# MICHAv2_0.net
KiCad netlist of a schematic drawn in EAGLE
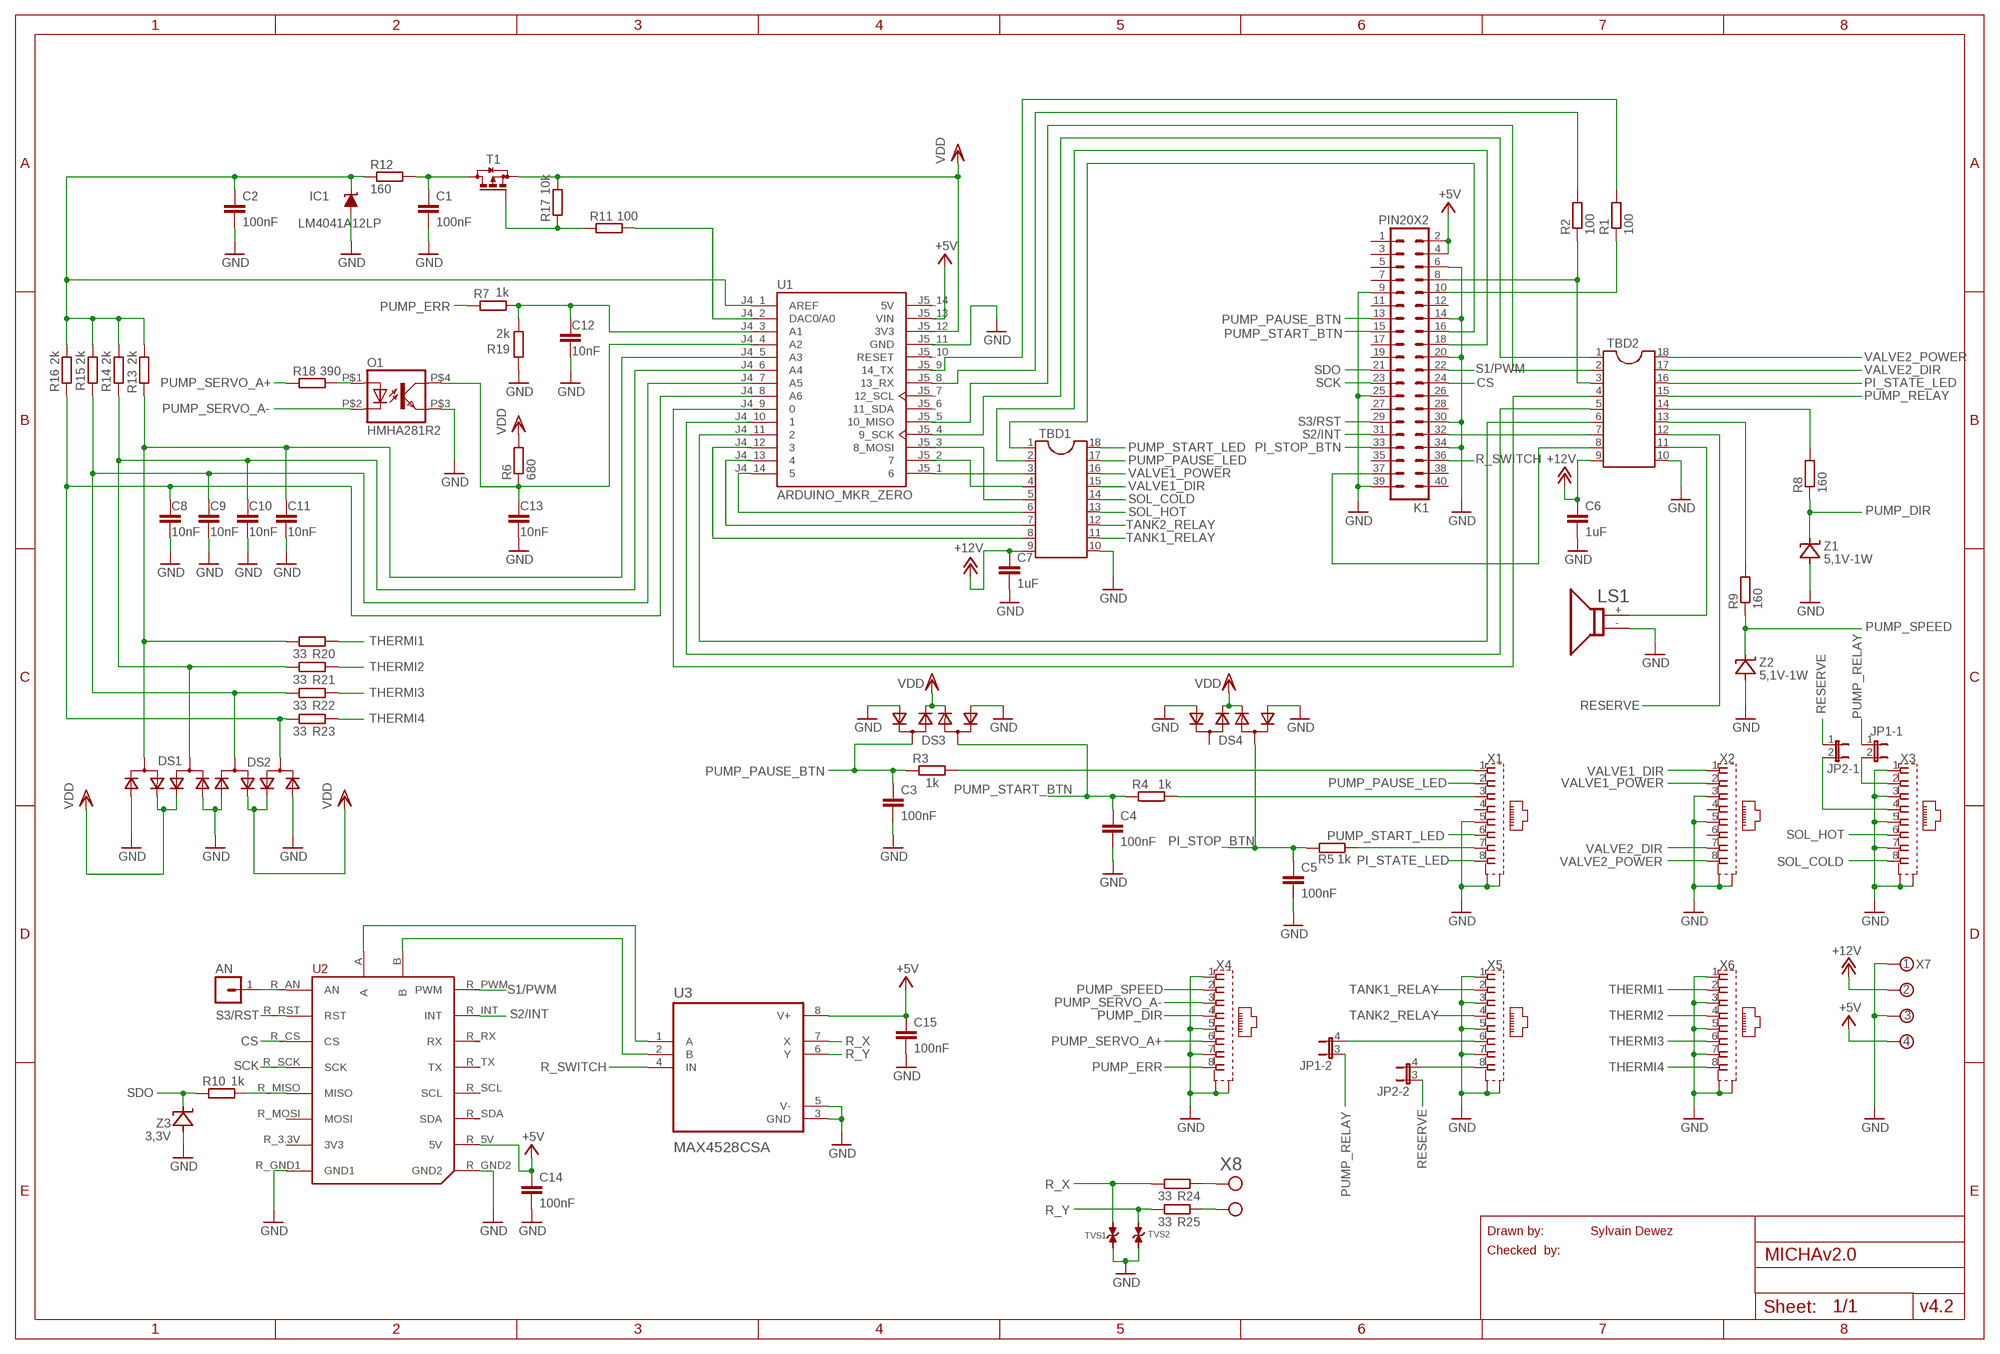
[diagram p0: schematic, sheet 1]

(export (version "E")
  (design (tool "Eeschema 10.0.6"))
  (components
    (comp (ref "AN")
      (value "MA01_PINHEADER")
      (footprint "eagle-import:MA01")
      (libsource (lib "eagle-import") (part "MA01_PINHEADER"))
    )
    (comp (ref "C1")
      (value "100nF")
      (footprint "eagle-import:C1206")
      (libsource (lib "eagle-import") (part "C-EUC1206"))
    )
    (comp (ref "C2")
      (value "100nF")
      (footprint "eagle-import:C1206")
      (libsource (lib "eagle-import") (part "C-EUC1206"))
    )
    (comp (ref "C3")
      (value "100nF")
      (footprint "eagle-import:C1206")
      (libsource (lib "eagle-import") (part "C-EUC1206"))
    )
    (comp (ref "C4")
      (value "100nF")
      (footprint "eagle-import:C1206")
      (libsource (lib "eagle-import") (part "C-EUC1206"))
    )
    (comp (ref "C5")
      (value "100nF")
      (footprint "eagle-import:C1206")
      (libsource (lib "eagle-import") (part "C-EUC1206"))
    )
    (comp (ref "C6")
      (value "1uF")
      (footprint "eagle-import:C1206")
      (libsource (lib "eagle-import") (part "C-EUC1206"))
    )
    (comp (ref "C7")
      (value "1uF")
      (footprint "eagle-import:C1206")
      (libsource (lib "eagle-import") (part "C-EUC1206"))
    )
    (comp (ref "C8")
      (value "10nF")
      (footprint "eagle-import:C1206")
      (libsource (lib "eagle-import") (part "C-EUC1206"))
    )
    (comp (ref "C9")
      (value "10nF")
      (footprint "eagle-import:C1206")
      (libsource (lib "eagle-import") (part "C-EUC1206"))
    )
    (comp (ref "C10")
      (value "10nF")
      (footprint "eagle-import:C1206")
      (libsource (lib "eagle-import") (part "C-EUC1206"))
    )
    (comp (ref "C11")
      (value "10nF")
      (footprint "eagle-import:C1206")
      (libsource (lib "eagle-import") (part "C-EUC1206"))
    )
    (comp (ref "C12")
      (value "10nF")
      (footprint "eagle-import:C1206")
      (libsource (lib "eagle-import") (part "C-EUC1206"))
    )
    (comp (ref "C13")
      (value "10nF")
      (footprint "eagle-import:C1206")
      (libsource (lib "eagle-import") (part "C-EUC1206"))
    )
    (comp (ref "C14")
      (value "100nF")
      (footprint "eagle-import:C1206")
      (libsource (lib "eagle-import") (part "C-EUC1206"))
    )
    (comp (ref "C15")
      (value "100nF")
      (footprint "eagle-import:C1206")
      (libsource (lib "eagle-import") (part "C-EUC1206"))
    )
    (comp (ref "DS1")
      (value "SDM10M45SD")
      (footprint "eagle-import:SDM10M45SD_SOT-26")
      (libsource (lib "eagle-import") (part "SDM10M45SD"))
    )
    (comp (ref "DS2")
      (value "SDM10M45SD")
      (footprint "eagle-import:SDM10M45SD_SOT-26")
      (libsource (lib "eagle-import") (part "SDM10M45SD"))
    )
    (comp (ref "DS3")
      (value "SDM10M45SD")
      (footprint "eagle-import:SDM10M45SD_SOT-26")
      (libsource (lib "eagle-import") (part "SDM10M45SD"))
    )
    (comp (ref "DS4")
      (value "SDM10M45SD")
      (footprint "eagle-import:SDM10M45SD_SOT-26")
      (libsource (lib "eagle-import") (part "SDM10M45SD"))
    )
    (comp (ref "IC1")
      (value "LM4041A12LP")
      (footprint "eagle-import:LP_O-PBCY-W3")
      (libsource (lib "eagle-import") (part "LM4041LPA12"))
    )
    (comp (ref "JP1")
      (value "JP2QE")
      (footprint "eagle-import:JP2Q")
      (libsource (lib "eagle-import") (part "JP2QE"))
    )
    (comp (ref "JP2")
      (value "JP2QE")
      (footprint "eagle-import:JP2Q")
      (libsource (lib "eagle-import") (part "JP2QE"))
    )
    (comp (ref "K1")
      (value "PIN20X2")
      (footprint "eagle-import:PIN_20X2")
      (libsource (lib "eagle-import") (part "PIN20X2"))
    )
    (comp (ref "LS1")
      (value "RSPRO-BUZZER-7800743")
      (footprint "eagle-import:RSPRO-BUZZER-7800743")
      (libsource (lib "eagle-import") (part "RSPRO-BUZZER-7800743"))
    )
    (comp (ref "O1")
      (value "HMHA281R2")
      (footprint "eagle-import:HMHA281R2")
      (libsource (lib "eagle-import") (part "HMHA281R2"))
    )
    (comp (ref "R1")
      (value "100")
      (footprint "eagle-import:R1206")
      (libsource (lib "eagle-import") (part "resistor_R-EU_R1206"))
    )
    (comp (ref "R2")
      (value "100")
      (footprint "eagle-import:R1206")
      (libsource (lib "eagle-import") (part "resistor_R-EU_R1206"))
    )
    (comp (ref "R3")
      (value "1k")
      (footprint "eagle-import:R1206")
      (libsource (lib "eagle-import") (part "resistor_R-EU_R1206"))
    )
    (comp (ref "R4")
      (value "1k")
      (footprint "eagle-import:R1206")
      (libsource (lib "eagle-import") (part "resistor_R-EU_R1206"))
    )
    (comp (ref "R5")
      (value "1k")
      (footprint "eagle-import:R1206")
      (libsource (lib "eagle-import") (part "resistor_R-EU_R1206"))
    )
    (comp (ref "R6")
      (value "680")
      (footprint "eagle-import:R1206")
      (libsource (lib "eagle-import") (part "resistor_R-EU_R1206"))
    )
    (comp (ref "R7")
      (value "1k")
      (footprint "eagle-import:R1206")
      (libsource (lib "eagle-import") (part "resistor_R-EU_R1206"))
    )
    (comp (ref "R8")
      (value "160")
      (footprint "eagle-import:R1206")
      (libsource (lib "eagle-import") (part "R-EU_R1206"))
    )
    (comp (ref "R9")
      (value "160")
      (footprint "eagle-import:R1206")
      (libsource (lib "eagle-import") (part "R-EU_R1206"))
    )
    (comp (ref "R10")
      (value "1k")
      (footprint "eagle-import:R1206")
      (libsource (lib "eagle-import") (part "resistor_R-EU_R1206"))
    )
    (comp (ref "R11")
      (value "100")
      (footprint "eagle-import:R1206")
      (libsource (lib "eagle-import") (part "resistor_R-EU_R1206"))
    )
    (comp (ref "R12")
      (value "160")
      (footprint "eagle-import:R1206")
      (libsource (lib "eagle-import") (part "R-EU_R1206"))
    )
    (comp (ref "R13")
      (value "2k")
      (footprint "eagle-import:R1206")
      (libsource (lib "eagle-import") (part "resistor_R-EU_R1206"))
    )
    (comp (ref "R14")
      (value "2k")
      (footprint "eagle-import:R1206")
      (libsource (lib "eagle-import") (part "resistor_R-EU_R1206"))
    )
    (comp (ref "R15")
      (value "2k")
      (footprint "eagle-import:R1206")
      (libsource (lib "eagle-import") (part "resistor_R-EU_R1206"))
    )
    (comp (ref "R16")
      (value "2k")
      (footprint "eagle-import:R1206")
      (libsource (lib "eagle-import") (part "resistor_R-EU_R1206"))
    )
    (comp (ref "R17")
      (value "10k")
      (footprint "eagle-import:R1206")
      (libsource (lib "eagle-import") (part "resistor_R-EU_R1206"))
    )
    (comp (ref "R18")
      (value "390")
      (footprint "eagle-import:R1206")
      (libsource (lib "eagle-import") (part "resistor_R-EU_R1206"))
    )
    (comp (ref "R19")
      (value "2k")
      (footprint "eagle-import:R1206")
      (libsource (lib "eagle-import") (part "resistor_R-EU_R1206"))
    )
    (comp (ref "R20")
      (value "33")
      (footprint "eagle-import:R1206")
      (libsource (lib "eagle-import") (part "resistor_R-EU_R1206"))
    )
    (comp (ref "R21")
      (value "33")
      (footprint "eagle-import:R1206")
      (libsource (lib "eagle-import") (part "resistor_R-EU_R1206"))
    )
    (comp (ref "R22")
      (value "33")
      (footprint "eagle-import:R1206")
      (libsource (lib "eagle-import") (part "resistor_R-EU_R1206"))
    )
    (comp (ref "R23")
      (value "33")
      (footprint "eagle-import:R1206")
      (libsource (lib "eagle-import") (part "resistor_R-EU_R1206"))
    )
    (comp (ref "R24")
      (value "33")
      (footprint "eagle-import:R1206")
      (libsource (lib "eagle-import") (part "resistor_R-EU_R1206"))
    )
    (comp (ref "R25")
      (value "33")
      (footprint "eagle-import:R1206")
      (libsource (lib "eagle-import") (part "resistor_R-EU_R1206"))
    )
    (comp (ref "T1")
      (value "BSS84")
      (footprint "eagle-import:SOT23")
      (libsource (lib "eagle-import") (part "BSS84"))
    )
    (comp (ref "TBD1")
      (value "DIL18S")
      (footprint "eagle-import:SOCKET-18")
      (libsource (lib "eagle-import") (part "DIL18S"))
    )
    (comp (ref "TBD2")
      (value "DIL18S")
      (footprint "eagle-import:SOCKET-18")
      (libsource (lib "eagle-import") (part "DIL18S"))
    )
    (comp (ref "TVS1")
      (value "TVS_SOD123")
      (footprint "eagle-import:TVS_SOD123")
      (libsource (lib "eagle-import") (part "TVS_SOD123"))
    )
    (comp (ref "TVS2")
      (value "TVS_SOD123")
      (footprint "eagle-import:TVS_SOD123")
      (libsource (lib "eagle-import") (part "TVS_SOD123"))
    )
    (comp (ref "U1")
      (value "ARDUINO_MKR_ZERO")
      (footprint "eagle-import:MODULE_ARDUINO_MKR_ZERO")
      (fields (field (name "MF") "Arduino") (field (name "MP") "ARDUINO MKR ZERO"))
      (libsource (lib "eagle-import") (part "ARDUINO_MKR_ZERO"))
    )
    (comp (ref "U2")
      (value "MIKROE_CLICK_UPGRADE")
      (footprint "eagle-import:MIKROE_BUS_MIDI_UPGRADE")
      (libsource (lib "eagle-import") (part "MIKROE_CLICK_UPGRADE"))
    )
    (comp (ref "U3")
      (value "MAX4528CSA")
      (footprint "eagle-import:SOIC127P600X175-8N")
      (fields (field (name "MF") "Maxim Integrated") (field (name "MP") "MAX4528CSA+"))
      (libsource (lib "eagle-import") (part "MAX4528CSA"))
    )
    (comp (ref "X1")
      (value "SS-7188S-A-NF_V2")
      (footprint "eagle-import:BEL_SS-7188S-A-NF")
      (fields (field (name "MF") "Stewart Connector") (field (name "MP") "SS-7188S-A-NF"))
      (libsource (lib "eagle-import") (part "SS-7188S-A-NF_V2"))
    )
    (comp (ref "X2")
      (value "SS-7188S-A-NF_V2")
      (footprint "eagle-import:BEL_SS-7188S-A-NF")
      (fields (field (name "MF") "Stewart Connector") (field (name "MP") "SS-7188S-A-NF"))
      (libsource (lib "eagle-import") (part "SS-7188S-A-NF_V2"))
    )
    (comp (ref "X3")
      (value "SS-7188S-A-NF_V2")
      (footprint "eagle-import:BEL_SS-7188S-A-NF")
      (fields (field (name "MF") "Stewart Connector") (field (name "MP") "SS-7188S-A-NF"))
      (libsource (lib "eagle-import") (part "SS-7188S-A-NF_V2"))
    )
    (comp (ref "X4")
      (value "SS-7188S-A-NF_V2")
      (footprint "eagle-import:BEL_SS-7188S-A-NF")
      (fields (field (name "MF") "Stewart Connector") (field (name "MP") "SS-7188S-A-NF"))
      (libsource (lib "eagle-import") (part "SS-7188S-A-NF_V2"))
    )
    (comp (ref "X5")
      (value "SS-7188S-A-NF_V2")
      (footprint "eagle-import:BEL_SS-7188S-A-NF")
      (fields (field (name "MF") "Stewart Connector") (field (name "MP") "SS-7188S-A-NF"))
      (libsource (lib "eagle-import") (part "SS-7188S-A-NF_V2"))
    )
    (comp (ref "X6")
      (value "SS-7188S-A-NF_V2")
      (footprint "eagle-import:BEL_SS-7188S-A-NF")
      (fields (field (name "MF") "Stewart Connector") (field (name "MP") "SS-7188S-A-NF"))
      (libsource (lib "eagle-import") (part "SS-7188S-A-NF_V2"))
    )
    (comp (ref "X7")
      (value "BUCHANAN_4_3.5MM")
      (footprint "eagle-import:BUCHANAN_4_3.5MM")
      (libsource (lib "eagle-import") (part "BUCHANAN_4_3.5MM"))
    )
    (comp (ref "X8")
      (value "MPT_0,5/_2-2,54_1725656_2")
      (footprint "eagle-import:PH_MPT_0,5__2-2,54_1725656")
      (fields (field (name "MF") "Phoenix Contact") (field (name "MP") "MPT 0,5/ 2-2,54 1725656"))
      (libsource (lib "eagle-import") (part "MPT_0,5/_2-2,54_1725656_2"))
    )
    (comp (ref "Z1")
      (value "5,1V-1W")
      (footprint "eagle-import:ZENER_SMA")
      (libsource (lib "eagle-import") (part "ZENER_SMA"))
    )
    (comp (ref "Z2")
      (value "5,1V-1W")
      (footprint "eagle-import:ZENER_SMA")
      (libsource (lib "eagle-import") (part "ZENER_SMA"))
    )
    (comp (ref "Z3")
      (value "3,3V")
      (footprint "eagle-import:ZENER_SMA")
      (libsource (lib "eagle-import") (part "ZENER_SMA"))
    )
  )
  (nets
    (net (code "1") (name "+5V") (class "Default")
      (node (ref "C14") (pin "1") (pinfunction "1_1") (pintype "passive"))
      (node (ref "C15") (pin "1") (pinfunction "1_1") (pintype "passive"))
      (node (ref "K1") (pin "2") (pinfunction "2_2") (pintype "passive"))
      (node (ref "K1") (pin "4") (pinfunction "4_4") (pintype "passive"))
      (node (ref "U1") (pin "J5_13") (pinfunction "VIN_J5_13") (pintype "power_in"))
      (node (ref "U2") (pin "R_5V") (pinfunction "5V_R_5V") (pintype "bidirectional"))
      (node (ref "U3") (pin "8") (pinfunction "V+_8") (pintype "power_in"))
      (node (ref "X7") (pin "4") (pinfunction "KL3_4") (pintype "passive"))
    )
    (net (code "2") (name "+12V") (class "Default")
      (node (ref "C6") (pin "1") (pinfunction "1_1") (pintype "passive"))
      (node (ref "C7") (pin "1") (pinfunction "1_1") (pintype "passive"))
      (node (ref "TBD1") (pin "9") (pinfunction "9_9") (pintype "passive"))
      (node (ref "TBD2") (pin "9") (pinfunction "9_9") (pintype "passive"))
      (node (ref "X7") (pin "2") (pinfunction "KL1_2") (pintype "passive"))
    )
    (net (code "3") (name "/5V") (class "Default")
      (node (ref "U1") (pin "J5_14") (pinfunction "5V_J5_14") (pintype "power_in"))
    )
    (net (code "4") (name "/CS") (class "Default")
      (node (ref "K1") (pin "24") (pinfunction "24_24") (pintype "passive"))
      (node (ref "U2") (pin "R_CS") (pinfunction "CS_R_CS") (pintype "bidirectional"))
    )
    (net (code "5") (name "/PI_STATE_LED") (class "Default")
      (node (ref "TBD2") (pin "16") (pinfunction "16_16") (pintype "passive"))
      (node (ref "X1") (pin "8") (pinfunction "8_8") (pintype "passive"))
    )
    (net (code "6") (name "/PI_STOP_BTN") (class "Default")
      (node (ref "C5") (pin "1") (pinfunction "1_1") (pintype "passive"))
      (node (ref "DS4") (pin "3") (pinfunction "C1_3") (pintype "passive"))
      (node (ref "K1") (pin "33") (pinfunction "33_33") (pintype "passive"))
      (node (ref "R5") (pin "1") (pinfunction "1_1") (pintype "passive"))
    )
    (net (code "7") (name "/PUMP_DIR") (class "Default")
      (node (ref "R8") (pin "1") (pinfunction "1_1") (pintype "passive"))
      (node (ref "X4") (pin "4") (pinfunction "4_4") (pintype "passive"))
      (node (ref "Z1") (pin "C") (pinfunction "C_C") (pintype "passive"))
    )
    (net (code "8") (name "/PUMP_ERR") (class "Default")
      (node (ref "R7") (pin "1") (pinfunction "1_1") (pintype "passive"))
      (node (ref "X4") (pin "8") (pinfunction "8_8") (pintype "passive"))
    )
    (net (code "9") (name "/PUMP_PAUSE_BTN") (class "Default")
      (node (ref "C3") (pin "1") (pinfunction "1_1") (pintype "passive"))
      (node (ref "DS3") (pin "6") (pinfunction "C_6") (pintype "passive"))
      (node (ref "K1") (pin "13") (pinfunction "13_13") (pintype "passive"))
      (node (ref "R3") (pin "1") (pinfunction "1_1") (pintype "passive"))
    )
    (net (code "10") (name "/PUMP_PAUSE_LED") (class "Default")
      (node (ref "TBD1") (pin "17") (pinfunction "17_17") (pintype "passive"))
      (node (ref "X1") (pin "2") (pinfunction "2_2") (pintype "passive"))
    )
    (net (code "11") (name "/PUMP_RELAY") (class "Default")
      (node (ref "JP1") (pin "1") (pinfunction "1_1") (pintype "passive"))
      (node (ref "JP1") (pin "3") (pinfunction "1_3") (pintype "passive"))
      (node (ref "TBD2") (pin "15") (pinfunction "15_15") (pintype "passive"))
    )
    (net (code "12") (name "/PUMP_SERVO_A+") (class "Default")
      (node (ref "R18") (pin "1") (pinfunction "1_1") (pintype "passive"))
      (node (ref "X4") (pin "6") (pinfunction "6_6") (pintype "passive"))
    )
    (net (code "13") (name "/PUMP_SERVO_A-") (class "Default")
      (node (ref "O1") (pin "P$2") (pinfunction "C_P$2") (pintype "passive"))
      (node (ref "X4") (pin "3") (pinfunction "3_3") (pintype "passive"))
    )
    (net (code "14") (name "/PUMP_SPEED") (class "Default")
      (node (ref "R9") (pin "1") (pinfunction "1_1") (pintype "passive"))
      (node (ref "X4") (pin "2") (pinfunction "2_2") (pintype "passive"))
      (node (ref "Z2") (pin "C") (pinfunction "C_C") (pintype "passive"))
    )
    (net (code "15") (name "/PUMP_START_BTN") (class "Default")
      (node (ref "C4") (pin "1") (pinfunction "1_1") (pintype "passive"))
      (node (ref "DS3") (pin "3") (pinfunction "C1_3") (pintype "passive"))
      (node (ref "K1") (pin "15") (pinfunction "15_15") (pintype "passive"))
      (node (ref "R4") (pin "1") (pinfunction "1_1") (pintype "passive"))
    )
    (net (code "16") (name "/PUMP_START_LED") (class "Default")
      (node (ref "TBD1") (pin "18") (pinfunction "18_18") (pintype "passive"))
      (node (ref "X1") (pin "6") (pinfunction "6_6") (pintype "passive"))
    )
    (net (code "17") (name "/RESERVE") (class "Default")
      (node (ref "JP2") (pin "1") (pinfunction "1_1") (pintype "passive"))
      (node (ref "JP2") (pin "3") (pinfunction "1_3") (pintype "passive"))
      (node (ref "TBD2") (pin "12") (pinfunction "12_12") (pintype "passive"))
    )
    (net (code "18") (name "/R_SWITCH") (class "Default")
      (node (ref "K1") (pin "36") (pinfunction "36_36") (pintype "passive"))
      (node (ref "U3") (pin "4") (pinfunction "IN_4") (pintype "input"))
    )
    (net (code "19") (name "/R_X") (class "Default")
      (node (ref "R24") (pin "1") (pinfunction "1_1") (pintype "passive"))
      (node (ref "TVS1") (pin "P$1") (pinfunction "C_P$1") (pintype "passive"))
      (node (ref "U3") (pin "7") (pinfunction "X_7") (pintype "output"))
    )
    (net (code "20") (name "/R_Y") (class "Default")
      (node (ref "R25") (pin "1") (pinfunction "1_1") (pintype "passive"))
      (node (ref "TVS2") (pin "P$1") (pinfunction "C_P$1") (pintype "passive"))
      (node (ref "U3") (pin "6") (pinfunction "Y_6") (pintype "output"))
    )
    (net (code "21") (name "/S1{slash}PWM") (class "Default")
      (node (ref "K1") (pin "22") (pinfunction "22_22") (pintype "passive"))
      (node (ref "U2") (pin "R_PWM") (pinfunction "PWM_R_PWM") (pintype "bidirectional"))
    )
    (net (code "22") (name "/S2{slash}INT") (class "Default")
      (node (ref "K1") (pin "31") (pinfunction "31_31") (pintype "passive"))
      (node (ref "U2") (pin "R_INT") (pinfunction "INT_R_INT") (pintype "bidirectional"))
    )
    (net (code "23") (name "/S3{slash}RST") (class "Default")
      (node (ref "K1") (pin "29") (pinfunction "29_29") (pintype "passive"))
      (node (ref "U2") (pin "R_RST") (pinfunction "RST_R_RST") (pintype "bidirectional"))
    )
    (net (code "24") (name "/SCK") (class "Default")
      (node (ref "K1") (pin "23") (pinfunction "23_23") (pintype "passive"))
      (node (ref "U2") (pin "R_SCK") (pinfunction "SCK_R_SCK") (pintype "bidirectional"))
    )
    (net (code "25") (name "/SDO") (class "Default")
      (node (ref "K1") (pin "21") (pinfunction "21_21") (pintype "passive"))
      (node (ref "R10") (pin "1") (pinfunction "1_1") (pintype "passive"))
      (node (ref "Z3") (pin "C") (pinfunction "C_C") (pintype "passive"))
    )
    (net (code "26") (name "/SOL_COLD") (class "Default")
      (node (ref "TBD1") (pin "14") (pinfunction "14_14") (pintype "passive"))
      (node (ref "X3") (pin "8") (pinfunction "8_8") (pintype "passive"))
    )
    (net (code "27") (name "/SOL_HOT") (class "Default")
      (node (ref "TBD1") (pin "13") (pinfunction "13_13") (pintype "passive"))
      (node (ref "X3") (pin "6") (pinfunction "6_6") (pintype "passive"))
    )
    (net (code "28") (name "/TANK1_RELAY") (class "Default")
      (node (ref "TBD1") (pin "11") (pinfunction "11_11") (pintype "passive"))
      (node (ref "X5") (pin "2") (pinfunction "2_2") (pintype "passive"))
    )
    (net (code "29") (name "/TANK2_RELAY") (class "Default")
      (node (ref "TBD1") (pin "12") (pinfunction "12_12") (pintype "passive"))
      (node (ref "X5") (pin "4") (pinfunction "4_4") (pintype "passive"))
    )
    (net (code "30") (name "/THERMI1") (class "Default")
      (node (ref "R20") (pin "2") (pinfunction "2_2") (pintype "passive"))
      (node (ref "X6") (pin "2") (pinfunction "2_2") (pintype "passive"))
    )
    (net (code "31") (name "/THERMI2") (class "Default")
      (node (ref "R21") (pin "2") (pinfunction "2_2") (pintype "passive"))
      (node (ref "X6") (pin "4") (pinfunction "4_4") (pintype "passive"))
    )
    (net (code "32") (name "/THERMI3") (class "Default")
      (node (ref "R22") (pin "2") (pinfunction "2_2") (pintype "passive"))
      (node (ref "X6") (pin "6") (pinfunction "6_6") (pintype "passive"))
    )
    (net (code "33") (name "/THERMI4") (class "Default")
      (node (ref "R23") (pin "2") (pinfunction "2_2") (pintype "passive"))
      (node (ref "X6") (pin "8") (pinfunction "8_8") (pintype "passive"))
    )
    (net (code "34") (name "/VALVE1_DIR") (class "Default")
      (node (ref "TBD1") (pin "15") (pinfunction "15_15") (pintype "passive"))
      (node (ref "X2") (pin "1") (pinfunction "1_1") (pintype "passive"))
    )
    (net (code "35") (name "/VALVE1_POWER") (class "Default")
      (node (ref "TBD1") (pin "16") (pinfunction "16_16") (pintype "passive"))
      (node (ref "X2") (pin "2") (pinfunction "2_2") (pintype "passive"))
    )
    (net (code "36") (name "/VALVE2_DIR") (class "Default")
      (node (ref "TBD2") (pin "17") (pinfunction "17_17") (pintype "passive"))
      (node (ref "X2") (pin "7") (pinfunction "7_7") (pintype "passive"))
    )
    (net (code "37") (name "/VALVE2_POWER") (class "Default")
      (node (ref "TBD2") (pin "18") (pinfunction "18_18") (pintype "passive"))
      (node (ref "X2") (pin "8") (pinfunction "8_8") (pintype "passive"))
    )
    (net (code "38") (name "GND") (class "Default")
      (node (ref "C1") (pin "2") (pinfunction "2_2") (pintype "passive"))
      (node (ref "C10") (pin "2") (pinfunction "2_2") (pintype "passive"))
      (node (ref "C11") (pin "2") (pinfunction "2_2") (pintype "passive"))
      (node (ref "C12") (pin "2") (pinfunction "2_2") (pintype "passive"))
      (node (ref "C13") (pin "2") (pinfunction "2_2") (pintype "passive"))
      (node (ref "C14") (pin "2") (pinfunction "2_2") (pintype "passive"))
      (node (ref "C15") (pin "2") (pinfunction "2_2") (pintype "passive"))
      (node (ref "C2") (pin "2") (pinfunction "2_2") (pintype "passive"))
      (node (ref "C3") (pin "2") (pinfunction "2_2") (pintype "passive"))
      (node (ref "C4") (pin "2") (pinfunction "2_2") (pintype "passive"))
      (node (ref "C5") (pin "2") (pinfunction "2_2") (pintype "passive"))
      (node (ref "C6") (pin "2") (pinfunction "2_2") (pintype "passive"))
      (node (ref "C7") (pin "2") (pinfunction "2_2") (pintype "passive"))
      (node (ref "C8") (pin "2") (pinfunction "2_2") (pintype "passive"))
      (node (ref "C9") (pin "2") (pinfunction "2_2") (pintype "passive"))
      (node (ref "DS1") (pin "1") (pinfunction "A2_1") (pintype "passive"))
      (node (ref "DS1") (pin "4") (pinfunction "A3_4") (pintype "passive"))
      (node (ref "DS2") (pin "1") (pinfunction "A2_1") (pintype "passive"))
      (node (ref "DS2") (pin "4") (pinfunction "A3_4") (pintype "passive"))
      (node (ref "DS3") (pin "1") (pinfunction "A2_1") (pintype "passive"))
      (node (ref "DS3") (pin "4") (pinfunction "A3_4") (pintype "passive"))
      (node (ref "DS4") (pin "1") (pinfunction "A2_1") (pintype "passive"))
      (node (ref "DS4") (pin "4") (pinfunction "A3_4") (pintype "passive"))
      (node (ref "IC1") (pin "3") (pinfunction "A_3") (pintype "passive"))
      (node (ref "K1") (pin "14") (pinfunction "14_14") (pintype "passive"))
      (node (ref "K1") (pin "20") (pinfunction "20_20") (pintype "passive"))
      (node (ref "K1") (pin "25") (pinfunction "25_25") (pintype "passive"))
      (node (ref "K1") (pin "30") (pinfunction "30_30") (pintype "passive"))
      (node (ref "K1") (pin "34") (pinfunction "34_34") (pintype "passive"))
      (node (ref "K1") (pin "39") (pinfunction "39_39") (pintype "passive"))
      (node (ref "K1") (pin "6") (pinfunction "6_6") (pintype "passive"))
      (node (ref "K1") (pin "9") (pinfunction "9_9") (pintype "passive"))
      (node (ref "LS1") (pin "-") (pinfunction "2_-") (pintype "passive"))
      (node (ref "O1") (pin "P$3") (pinfunction "EMIT_P$3") (pintype "passive"))
      (node (ref "R19") (pin "1") (pinfunction "1_1") (pintype "passive"))
      (node (ref "TBD1") (pin "10") (pinfunction "10_10") (pintype "passive"))
      (node (ref "TBD2") (pin "10") (pinfunction "10_10") (pintype "passive"))
      (node (ref "TVS1") (pin "P$2") (pinfunction "C1_P$2") (pintype "passive"))
      (node (ref "TVS2") (pin "P$2") (pinfunction "C1_P$2") (pintype "passive"))
      (node (ref "U1") (pin "J5_11") (pinfunction "GND_J5_11") (pintype "power_in"))
      (node (ref "U2") (pin "R_GND1") (pinfunction "GND1_R_GND1") (pintype "bidirectional"))
      (node (ref "U2") (pin "R_GND2") (pinfunction "GND2_R_GND2") (pintype "bidirectional"))
      (node (ref "U3") (pin "3") (pinfunction "GND_3") (pintype "power_in"))
      (node (ref "U3") (pin "5") (pinfunction "V-_5") (pintype "power_in"))
      (node (ref "X1") (pin "5") (pinfunction "5_5") (pintype "passive"))
      (node (ref "X1") (pin "S1") (pinfunction "GND1_S1") (pintype "passive"))
      (node (ref "X1") (pin "S2") (pinfunction "GND2_S2") (pintype "passive"))
      (node (ref "X2") (pin "3") (pinfunction "3_3") (pintype "passive"))
      (node (ref "X2") (pin "5") (pinfunction "5_5") (pintype "passive"))
      (node (ref "X2") (pin "S1") (pinfunction "GND1_S1") (pintype "passive"))
      (node (ref "X2") (pin "S2") (pinfunction "GND2_S2") (pintype "passive"))
      (node (ref "X3") (pin "1") (pinfunction "1_1") (pintype "passive"))
      (node (ref "X3") (pin "3") (pinfunction "3_3") (pintype "passive"))
      (node (ref "X3") (pin "5") (pinfunction "5_5") (pintype "passive"))
      (node (ref "X3") (pin "7") (pinfunction "7_7") (pintype "passive"))
      (node (ref "X3") (pin "S1") (pinfunction "GND1_S1") (pintype "passive"))
      (node (ref "X3") (pin "S2") (pinfunction "GND2_S2") (pintype "passive"))
      (node (ref "X4") (pin "1") (pinfunction "1_1") (pintype "passive"))
      (node (ref "X4") (pin "5") (pinfunction "5_5") (pintype "passive"))
      (node (ref "X4") (pin "7") (pinfunction "7_7") (pintype "passive"))
      (node (ref "X4") (pin "S1") (pinfunction "GND1_S1") (pintype "passive"))
      (node (ref "X4") (pin "S2") (pinfunction "GND2_S2") (pintype "passive"))
      (node (ref "X5") (pin "1") (pinfunction "1_1") (pintype "passive"))
      (node (ref "X5") (pin "3") (pinfunction "3_3") (pintype "passive"))
      (node (ref "X5") (pin "5") (pinfunction "5_5") (pintype "passive"))
      (node (ref "X5") (pin "7") (pinfunction "7_7") (pintype "passive"))
      (node (ref "X5") (pin "S1") (pinfunction "GND1_S1") (pintype "passive"))
      (node (ref "X5") (pin "S2") (pinfunction "GND2_S2") (pintype "passive"))
      (node (ref "X6") (pin "1") (pinfunction "1_1") (pintype "passive"))
      (node (ref "X6") (pin "3") (pinfunction "3_3") (pintype "passive"))
      (node (ref "X6") (pin "5") (pinfunction "5_5") (pintype "passive"))
      (node (ref "X6") (pin "7") (pinfunction "7_7") (pintype "passive"))
      (node (ref "X6") (pin "S1") (pinfunction "GND1_S1") (pintype "passive"))
      (node (ref "X6") (pin "S2") (pinfunction "GND2_S2") (pintype "passive"))
      (node (ref "X7") (pin "1") (pinfunction "KL_1") (pintype "passive"))
      (node (ref "X7") (pin "3") (pinfunction "KL2_3") (pintype "passive"))
      (node (ref "Z1") (pin "A") (pinfunction "A_A") (pintype "passive"))
      (node (ref "Z2") (pin "A") (pinfunction "A_A") (pintype "passive"))
      (node (ref "Z3") (pin "A") (pinfunction "A_A") (pintype "passive"))
    )
    (net (code "39") (name "Net-(DS1-C)") (class "Default")
      (node (ref "C10") (pin "1") (pinfunction "1_1") (pintype "passive"))
      (node (ref "DS1") (pin "6") (pinfunction "C_6") (pintype "passive"))
      (node (ref "R14") (pin "2") (pinfunction "2_2") (pintype "passive"))
      (node (ref "R21") (pin "1") (pinfunction "1_1") (pintype "passive"))
      (node (ref "U1") (pin "J4_6") (pinfunction "A4_J4_6") (pintype "bidirectional"))
    )
    (net (code "40") (name "Net-(DS1-C1)") (class "Default")
      (node (ref "C11") (pin "1") (pinfunction "1_1") (pintype "passive"))
      (node (ref "DS1") (pin "3") (pinfunction "C1_3") (pintype "passive"))
      (node (ref "R13") (pin "2") (pinfunction "2_2") (pintype "passive"))
      (node (ref "R20") (pin "1") (pinfunction "1_1") (pintype "passive"))
      (node (ref "U1") (pin "J4_5") (pinfunction "A3_J4_5") (pintype "bidirectional"))
    )
    (net (code "41") (name "Net-(DS2-C)") (class "Default")
      (node (ref "C8") (pin "1") (pinfunction "1_1") (pintype "passive"))
      (node (ref "DS2") (pin "6") (pinfunction "C_6") (pintype "passive"))
      (node (ref "R16") (pin "2") (pinfunction "2_2") (pintype "passive"))
      (node (ref "R23") (pin "1") (pinfunction "1_1") (pintype "passive"))
      (node (ref "U1") (pin "J4_8") (pinfunction "A6_J4_8") (pintype "bidirectional"))
    )
    (net (code "42") (name "Net-(DS2-C1)") (class "Default")
      (node (ref "C9") (pin "1") (pinfunction "1_1") (pintype "passive"))
      (node (ref "DS2") (pin "3") (pinfunction "C1_3") (pintype "passive"))
      (node (ref "R15") (pin "2") (pinfunction "2_2") (pintype "passive"))
      (node (ref "R22") (pin "1") (pinfunction "1_1") (pintype "passive"))
      (node (ref "U1") (pin "J4_7") (pinfunction "A5_J4_7") (pintype "bidirectional"))
    )
    (net (code "43") (name "Net-(IC1-C)") (class "Default")
      (node (ref "C2") (pin "1") (pinfunction "1_1") (pintype "passive"))
      (node (ref "IC1") (pin "2") (pinfunction "C_2") (pintype "passive"))
      (node (ref "R12") (pin "1") (pinfunction "1_1") (pintype "passive"))
      (node (ref "R13") (pin "1") (pinfunction "1_1") (pintype "passive"))
      (node (ref "R14") (pin "1") (pinfunction "1_1") (pintype "passive"))
      (node (ref "R15") (pin "1") (pinfunction "1_1") (pintype "passive"))
      (node (ref "R16") (pin "1") (pinfunction "1_1") (pintype "passive"))
      (node (ref "U1") (pin "J4_1") (pinfunction "AREF_J4_1") (pintype "bidirectional"))
    )
    (net (code "44") (name "Net-(JP1-Pad2)") (class "Default")
      (node (ref "JP1") (pin "2") (pinfunction "2_2") (pintype "passive"))
      (node (ref "X3") (pin "2") (pinfunction "2_2") (pintype "passive"))
    )
    (net (code "45") (name "Net-(JP1B-2)") (class "Default")
      (node (ref "JP1") (pin "4") (pinfunction "2_4") (pintype "passive"))
      (node (ref "X5") (pin "6") (pinfunction "6_6") (pintype "passive"))
    )
    (net (code "46") (name "Net-(JP2-Pad2)") (class "Default")
      (node (ref "JP2") (pin "2") (pinfunction "2_2") (pintype "passive"))
      (node (ref "X3") (pin "4") (pinfunction "4_4") (pintype "passive"))
    )
    (net (code "47") (name "Net-(JP2B-2)") (class "Default")
      (node (ref "JP2") (pin "4") (pinfunction "2_4") (pintype "passive"))
      (node (ref "X5") (pin "8") (pinfunction "8_8") (pintype "passive"))
    )
    (net (code "48") (name "Net-(K1-Pad8)") (class "Default")
      (node (ref "K1") (pin "8") (pinfunction "8_8") (pintype "passive"))
      (node (ref "R2") (pin "1") (pinfunction "1_1") (pintype "passive"))
      (node (ref "TBD2") (pin "3") (pinfunction "3_3") (pintype "passive"))
    )
    (net (code "49") (name "Net-(K1-Pad10)") (class "Default")
      (node (ref "K1") (pin "10") (pinfunction "10_10") (pintype "passive"))
      (node (ref "R1") (pin "1") (pinfunction "1_1") (pintype "passive"))
    )
    (net (code "50") (name "Net-(K1-Pad16)") (class "Default")
      (node (ref "K1") (pin "16") (pinfunction "16_16") (pintype "passive"))
      (node (ref "TBD1") (pin "1") (pinfunction "1_1") (pintype "passive"))
    )
    (net (code "51") (name "Net-(K1-Pad18)") (class "Default")
      (node (ref "K1") (pin "18") (pinfunction "18_18") (pintype "passive"))
      (node (ref "TBD1") (pin "2") (pinfunction "2_2") (pintype "passive"))
    )
    (net (code "52") (name "Net-(K1-Pad32)") (class "Default")
      (node (ref "K1") (pin "32") (pinfunction "32_32") (pintype "passive"))
      (node (ref "TBD2") (pin "7") (pinfunction "7_7") (pintype "passive"))
    )
    (net (code "53") (name "Net-(K1-Pad37)") (class "Default")
      (node (ref "K1") (pin "37") (pinfunction "37_37") (pintype "passive"))
      (node (ref "TBD2") (pin "8") (pinfunction "8_8") (pintype "passive"))
    )
    (net (code "54") (name "Net-(LS1-1)") (class "Default")
      (node (ref "LS1") (pin "+") (pinfunction "1_+") (pintype "passive"))
      (node (ref "TBD2") (pin "11") (pinfunction "11_11") (pintype "passive"))
    )
    (net (code "55") (name "Net-(O1-A)") (class "Default")
      (node (ref "O1") (pin "P$1") (pinfunction "A_P$1") (pintype "passive"))
      (node (ref "R18") (pin "2") (pinfunction "2_2") (pintype "passive"))
    )
    (net (code "56") (name "Net-(O1-COL)") (class "Default")
      (node (ref "C13") (pin "1") (pinfunction "1_1") (pintype "passive"))
      (node (ref "O1") (pin "P$4") (pinfunction "COL_P$4") (pintype "passive"))
      (node (ref "R6") (pin "1") (pinfunction "1_1") (pintype "passive"))
      (node (ref "U1") (pin "J4_4") (pinfunction "A2_J4_4") (pintype "bidirectional"))
    )
    (net (code "57") (name "Net-(R3-Pad2)") (class "Default")
      (node (ref "R3") (pin "2") (pinfunction "2_2") (pintype "passive"))
      (node (ref "X1") (pin "1") (pinfunction "1_1") (pintype "passive"))
    )
    (net (code "58") (name "Net-(R4-Pad2)") (class "Default")
      (node (ref "R4") (pin "2") (pinfunction "2_2") (pintype "passive"))
      (node (ref "X1") (pin "3") (pinfunction "3_3") (pintype "passive"))
    )
    (net (code "59") (name "Net-(R5-Pad2)") (class "Default")
      (node (ref "R5") (pin "2") (pinfunction "2_2") (pintype "passive"))
      (node (ref "X1") (pin "7") (pinfunction "7_7") (pintype "passive"))
    )
    (net (code "60") (name "Net-(R8-Pad2)") (class "Default")
      (node (ref "R8") (pin "2") (pinfunction "2_2") (pintype "passive"))
      (node (ref "TBD2") (pin "14") (pinfunction "14_14") (pintype "passive"))
    )
    (net (code "61") (name "Net-(R9-Pad2)") (class "Default")
      (node (ref "R9") (pin "2") (pinfunction "2_2") (pintype "passive"))
      (node (ref "TBD2") (pin "13") (pinfunction "13_13") (pintype "passive"))
    )
    (net (code "62") (name "Net-(T1-D)") (class "Default")
      (node (ref "C1") (pin "1") (pinfunction "1_1") (pintype "passive"))
      (node (ref "R12") (pin "2") (pinfunction "2_2") (pintype "passive"))
      (node (ref "T1") (pin "3") (pinfunction "D_3") (pintype "passive"))
    )
    (net (code "63") (name "Net-(T1-G)") (class "Default")
      (node (ref "R11") (pin "1") (pinfunction "1_1") (pintype "passive"))
      (node (ref "R17") (pin "1") (pinfunction "1_1") (pintype "passive"))
      (node (ref "T1") (pin "1") (pinfunction "G_1") (pintype "passive"))
    )
    (net (code "64") (name "Net-(U1-0)") (class "Default")
      (node (ref "TBD2") (pin "4") (pinfunction "4_4") (pintype "passive"))
      (node (ref "U1") (pin "J4_9") (pinfunction "0_J4_9") (pintype "bidirectional"))
    )
    (net (code "65") (name "Net-(U1-1)") (class "Default")
      (node (ref "TBD2") (pin "5") (pinfunction "5_5") (pintype "passive"))
      (node (ref "U1") (pin "J4_10") (pinfunction "1_J4_10") (pintype "bidirectional"))
    )
    (net (code "66") (name "Net-(U1-2)") (class "Default")
      (node (ref "TBD2") (pin "6") (pinfunction "6_6") (pintype "passive"))
      (node (ref "U1") (pin "J4_11") (pinfunction "2_J4_11") (pintype "bidirectional"))
    )
    (net (code "67") (name "Net-(U1-3)") (class "Default")
      (node (ref "TBD1") (pin "8") (pinfunction "8_8") (pintype "passive"))
      (node (ref "U1") (pin "J4_12") (pinfunction "3_J4_12") (pintype "bidirectional"))
    )
    (net (code "68") (name "Net-(U1-4)") (class "Default")
      (node (ref "TBD1") (pin "7") (pinfunction "7_7") (pintype "passive"))
      (node (ref "U1") (pin "J4_13") (pinfunction "4_J4_13") (pintype "bidirectional"))
    )
    (net (code "69") (name "Net-(U1-5)") (class "Default")
      (node (ref "TBD1") (pin "6") (pinfunction "6_6") (pintype "passive"))
      (node (ref "U1") (pin "J4_14") (pinfunction "5_J4_14") (pintype "bidirectional"))
    )
    (net (code "70") (name "Net-(U1-6)") (class "Default")
      (node (ref "TBD1") (pin "3") (pinfunction "3_3") (pintype "passive"))
      (node (ref "U1") (pin "J5_1") (pinfunction "6_J5_1") (pintype "bidirectional"))
    )
    (net (code "71") (name "Net-(U1-7)") (class "Default")
      (node (ref "TBD1") (pin "4") (pinfunction "4_4") (pintype "passive"))
      (node (ref "U1") (pin "J5_2") (pinfunction "7_J5_2") (pintype "bidirectional"))
    )
    (net (code "72") (name "Net-(U1-8_MOSI)") (class "Default")
      (node (ref "TBD1") (pin "5") (pinfunction "5_5") (pintype "passive"))
      (node (ref "U1") (pin "J5_3") (pinfunction "8_MOSI_J5_3") (pintype "bidirectional"))
    )
    (net (code "73") (name "Net-(U1-9_SCK)") (class "Default")
      (node (ref "TBD2") (pin "1") (pinfunction "1_1") (pintype "passive"))
      (node (ref "U1") (pin "J5_4") (pinfunction "9_SCK_J5_4") (pintype "bidirectional"))
    )
    (net (code "74") (name "Net-(U1-10_MISO)") (class "Default")
      (node (ref "TBD2") (pin "2") (pinfunction "2_2") (pintype "passive"))
      (node (ref "U1") (pin "J5_5") (pinfunction "10_MISO_J5_5") (pintype "bidirectional"))
    )
    (net (code "75") (name "Net-(U1-13_RX)") (class "Default")
      (node (ref "R2") (pin "2") (pinfunction "2_2") (pintype "passive"))
      (node (ref "U1") (pin "J5_8") (pinfunction "13_RX_J5_8") (pintype "input"))
    )
    (net (code "76") (name "Net-(U1-14_TX)") (class "Default")
      (node (ref "R1") (pin "2") (pinfunction "2_2") (pintype "passive"))
      (node (ref "U1") (pin "J5_9") (pinfunction "14_TX_J5_9") (pintype "output"))
    )
    (net (code "77") (name "Net-(U1-A1)") (class "Default")
      (node (ref "C12") (pin "1") (pinfunction "1_1") (pintype "passive"))
      (node (ref "R19") (pin "2") (pinfunction "2_2") (pintype "passive"))
      (node (ref "R7") (pin "2") (pinfunction "2_2") (pintype "passive"))
      (node (ref "U1") (pin "J4_3") (pinfunction "A1_J4_3") (pintype "bidirectional"))
    )
    (net (code "78") (name "Net-(U1-DAC0{slash}A0)") (class "Default")
      (node (ref "R11") (pin "2") (pinfunction "2_2") (pintype "passive"))
      (node (ref "U1") (pin "J4_2") (pinfunction "DAC0/A0_J4_2") (pintype "bidirectional"))
    )
    (net (code "79") (name "Net-(U2-AN)") (class "Default")
      (node (ref "AN") (pin "1") (pinfunction "1_1") (pintype "passive"))
      (node (ref "U2") (pin "R_AN") (pinfunction "AN_R_AN") (pintype "bidirectional"))
    )
    (net (code "80") (name "Net-(U2-MISO)") (class "Default")
      (node (ref "R10") (pin "2") (pinfunction "2_2") (pintype "passive"))
      (node (ref "U2") (pin "R_MISO") (pinfunction "MISO_R_MISO") (pintype "bidirectional"))
    )
    (net (code "81") (name "Net-(U3-A)") (class "Default")
      (node (ref "U2") (pin "A") (pinfunction "A_A") (pintype "bidirectional"))
      (node (ref "U3") (pin "1") (pinfunction "A_1") (pintype "input"))
    )
    (net (code "82") (name "Net-(U3-B)") (class "Default")
      (node (ref "U2") (pin "B") (pinfunction "B_B") (pintype "bidirectional"))
      (node (ref "U3") (pin "2") (pinfunction "B_2") (pintype "input"))
    )
    (net (code "83") (name "Net-(X8-KL)") (class "Default")
      (node (ref "R25") (pin "2") (pinfunction "2_2") (pintype "passive"))
      (node (ref "X8") (pin "1") (pinfunction "KL_1") (pintype "passive"))
    )
    (net (code "84") (name "Net-(X8-KL1)") (class "Default")
      (node (ref "R24") (pin "2") (pinfunction "2_2") (pintype "passive"))
      (node (ref "X8") (pin "2") (pinfunction "KL1_2") (pintype "passive"))
    )
    (net (code "85") (name "VDD") (class "Default")
      (node (ref "DS1") (pin "2") (pinfunction "A1_2") (pintype "passive"))
      (node (ref "DS1") (pin "5") (pinfunction "A4_5") (pintype "passive"))
      (node (ref "DS2") (pin "2") (pinfunction "A1_2") (pintype "passive"))
      (node (ref "DS2") (pin "5") (pinfunction "A4_5") (pintype "passive"))
      (node (ref "DS3") (pin "2") (pinfunction "A1_2") (pintype "passive"))
      (node (ref "DS3") (pin "5") (pinfunction "A4_5") (pintype "passive"))
      (node (ref "DS4") (pin "2") (pinfunction "A1_2") (pintype "passive"))
      (node (ref "DS4") (pin "5") (pinfunction "A4_5") (pintype "passive"))
      (node (ref "R17") (pin "2") (pinfunction "2_2") (pintype "passive"))
      (node (ref "R6") (pin "2") (pinfunction "2_2") (pintype "passive"))
      (node (ref "T1") (pin "2") (pinfunction "S_2") (pintype "passive"))
      (node (ref "U1") (pin "J5_12") (pinfunction "3V3_J5_12") (pintype "power_in"))
    )
    (net (code "86") (name "unconnected-(DS4-C-Pad6)") (class "Default")
      (node (ref "DS4") (pin "6") (pinfunction "C_6") (pintype "passive"))
    )
    (net (code "87") (name "unconnected-(K1-Pad1)") (class "Default")
      (node (ref "K1") (pin "1") (pinfunction "1_1") (pintype "passive"))
    )
    (net (code "88") (name "unconnected-(K1-Pad3)") (class "Default")
      (node (ref "K1") (pin "3") (pinfunction "3_3") (pintype "passive"))
    )
    (net (code "89") (name "unconnected-(K1-Pad5)") (class "Default")
      (node (ref "K1") (pin "5") (pinfunction "5_5") (pintype "passive"))
    )
    (net (code "90") (name "unconnected-(K1-Pad7)") (class "Default")
      (node (ref "K1") (pin "7") (pinfunction "7_7") (pintype "passive"))
    )
    (net (code "91") (name "unconnected-(K1-Pad11)") (class "Default")
      (node (ref "K1") (pin "11") (pinfunction "11_11") (pintype "passive"))
    )
    (net (code "92") (name "unconnected-(K1-Pad12)") (class "Default")
      (node (ref "K1") (pin "12") (pinfunction "12_12") (pintype "passive"))
    )
    (net (code "93") (name "unconnected-(K1-Pad17)") (class "Default")
      (node (ref "K1") (pin "17") (pinfunction "17_17") (pintype "passive"))
    )
    (net (code "94") (name "unconnected-(K1-Pad19)") (class "Default")
      (node (ref "K1") (pin "19") (pinfunction "19_19") (pintype "passive"))
    )
    (net (code "95") (name "unconnected-(K1-Pad26)") (class "Default")
      (node (ref "K1") (pin "26") (pinfunction "26_26") (pintype "passive"))
    )
    (net (code "96") (name "unconnected-(K1-Pad27)") (class "Default")
      (node (ref "K1") (pin "27") (pinfunction "27_27") (pintype "passive"))
    )
    (net (code "97") (name "unconnected-(K1-Pad28)") (class "Default")
      (node (ref "K1") (pin "28") (pinfunction "28_28") (pintype "passive"))
    )
    (net (code "98") (name "unconnected-(K1-Pad35)") (class "Default")
      (node (ref "K1") (pin "35") (pinfunction "35_35") (pintype "passive"))
    )
    (net (code "99") (name "unconnected-(K1-Pad38)") (class "Default")
      (node (ref "K1") (pin "38") (pinfunction "38_38") (pintype "passive"))
    )
    (net (code "100") (name "unconnected-(K1-Pad40)") (class "Default")
      (node (ref "K1") (pin "40") (pinfunction "40_40") (pintype "passive"))
    )
    (net (code "101") (name "unconnected-(U1-11_SDA-PadJ5_6)") (class "Default")
      (node (ref "U1") (pin "J5_6") (pinfunction "11_SDA_J5_6") (pintype "bidirectional"))
    )
    (net (code "102") (name "unconnected-(U1-12_SCL-PadJ5_7)") (class "Default")
      (node (ref "U1") (pin "J5_7") (pinfunction "12_SCL_J5_7") (pintype "bidirectional"))
    )
    (net (code "103") (name "unconnected-(U1-RESET-PadJ5_10)") (class "Default")
      (node (ref "U1") (pin "J5_10") (pinfunction "RESET_J5_10") (pintype "bidirectional"))
    )
    (net (code "104") (name "unconnected-(U2-3V3-PadR_3.3V)") (class "Default")
      (node (ref "U2") (pin "R_3.3V") (pinfunction "3V3_R_3.3V") (pintype "bidirectional"))
    )
    (net (code "105") (name "unconnected-(U2-MOSI-PadR_MOSI)") (class "Default")
      (node (ref "U2") (pin "R_MOSI") (pinfunction "MOSI_R_MOSI") (pintype "bidirectional"))
    )
    (net (code "106") (name "unconnected-(U2-RX-PadR_RX)") (class "Default")
      (node (ref "U2") (pin "R_RX") (pinfunction "RX_R_RX") (pintype "bidirectional"))
    )
    (net (code "107") (name "unconnected-(U2-SCL-PadR_SCL)") (class "Default")
      (node (ref "U2") (pin "R_SCL") (pinfunction "SCL_R_SCL") (pintype "bidirectional"))
    )
    (net (code "108") (name "unconnected-(U2-SDA-PadR_SDA)") (class "Default")
      (node (ref "U2") (pin "R_SDA") (pinfunction "SDA_R_SDA") (pintype "bidirectional"))
    )
    (net (code "109") (name "unconnected-(U2-TX-PadR_TX)") (class "Default")
      (node (ref "U2") (pin "R_TX") (pinfunction "TX_R_TX") (pintype "bidirectional"))
    )
    (net (code "110") (name "unconnected-(X1-Pad4)") (class "Default")
      (node (ref "X1") (pin "4") (pinfunction "4_4") (pintype "passive"))
    )
    (net (code "111") (name "unconnected-(X2-Pad4)") (class "Default")
      (node (ref "X2") (pin "4") (pinfunction "4_4") (pintype "passive"))
    )
    (net (code "112") (name "unconnected-(X2-Pad6)") (class "Default")
      (node (ref "X2") (pin "6") (pinfunction "6_6") (pintype "passive"))
    )
  )
)
